# 27128_27256_Multi-ROM_Rev_4.net
KiCad netlist of a schematic drawn in EAGLE
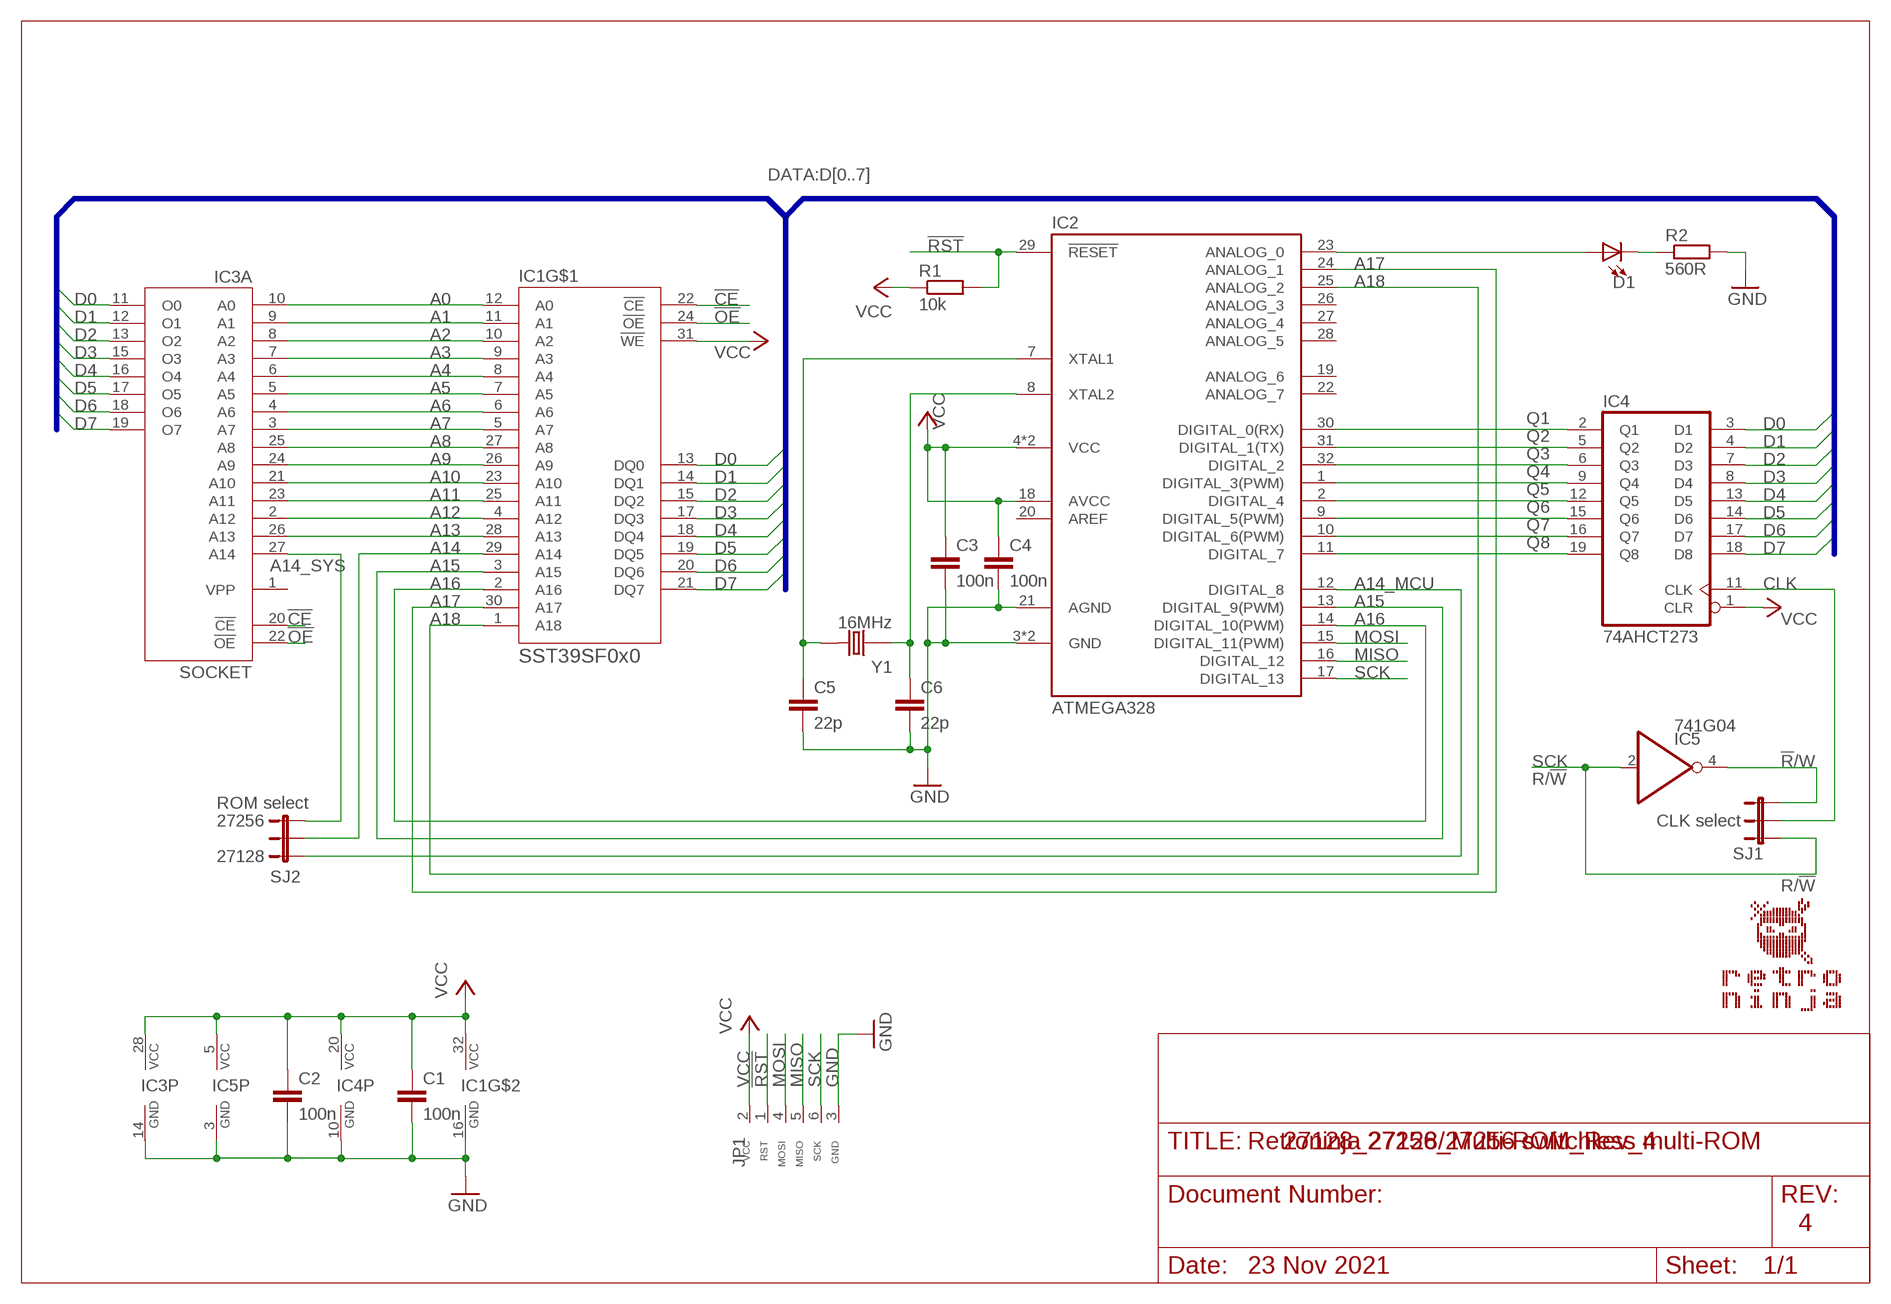
[diagram p0: schematic, sheet 1]

(export (version "E")
  (design (tool "Eeschema 10.0.6"))
  (components
    (comp (ref "C1")
      (value "100n")
      (footprint "eagle-import:C0805")
      (libsource (lib "eagle-import") (part "C-EUC0805"))
    )
    (comp (ref "C2")
      (value "100n")
      (footprint "eagle-import:C0805")
      (libsource (lib "eagle-import") (part "C-EUC0805"))
    )
    (comp (ref "C3")
      (value "100n")
      (footprint "eagle-import:C0805")
      (libsource (lib "eagle-import") (part "C-EUC0805"))
    )
    (comp (ref "C4")
      (value "100n")
      (footprint "eagle-import:C0805")
      (libsource (lib "eagle-import") (part "C-EUC0805"))
    )
    (comp (ref "C5")
      (value "22p")
      (footprint "eagle-import:C0805")
      (libsource (lib "eagle-import") (part "C-EUC0805"))
    )
    (comp (ref "C6")
      (value "22p")
      (footprint "eagle-import:C0805")
      (libsource (lib "eagle-import") (part "C-EUC0805"))
    )
    (comp (ref "D1")
      (value "LED_0805")
      (footprint "eagle-import:LED0805")
      (libsource (lib "eagle-import") (part "LED_0805"))
    )
    (comp (ref "IC1")
      (value "SST39SF0x0")
      (footprint "eagle-import:PLCC32_SHORT")
      (libsource (lib "eagle-import") (part "SST39XX040_PLCC_SHORT"))
    )
    (comp (ref "IC2")
      (value "ATMEGA328")
      (footprint "eagle-import:TQFP32")
      (libsource (lib "eagle-import") (part "ARDUINO_168_328_TQFP"))
    )
    (comp (ref "IC3")
      (value "SOCKET")
      (footprint "eagle-import:DIL28-6_DOWNPINS")
      (libsource (lib "eagle-import") (part "27C256_DOWNPINS"))
    )
    (comp (ref "IC4")
      (value "74AHCT273")
      (footprint "eagle-import:SO20")
      (libsource (lib "eagle-import") (part "74273NS"))
    )
    (comp (ref "IC5")
      (value "741G04")
      (footprint "eagle-import:SOT23-5")
      (libsource (lib "eagle-import") (part "741G04_SOT23"))
    )
    (comp (ref "JP1")
      (value "ICSP_CONNECTOR_TL866_RIGHT2")
      (footprint "eagle-import:HEADER_1X6_RIGHT")
      (libsource (lib "eagle-import") (part "ICSP_CONNECTOR_TL866_RIGHT2"))
    )
    (comp (ref "R1")
      (value "10k")
      (footprint "eagle-import:R0805")
      (libsource (lib "eagle-import") (part "R-EU_R0805"))
    )
    (comp (ref "R2")
      (value "560R")
      (footprint "eagle-import:R0805")
      (libsource (lib "eagle-import") (part "R-EU_R0805"))
    )
    (comp (ref "SJ1")
      (value "JUMPER-3SJ")
      (footprint "eagle-import:SJ-3")
      (libsource (lib "eagle-import") (part "JUMPER-3SJ"))
    )
    (comp (ref "SJ2")
      (value "JUMPER-3SJ")
      (footprint "eagle-import:SJ-3")
      (libsource (lib "eagle-import") (part "JUMPER-3SJ"))
    )
    (comp (ref "Y1")
      (value "16MHz")
      (footprint "eagle-import:CRYSTAL_SMD-2_7X4X2.3")
      (libsource (lib "eagle-import") (part "CRYSTAL"))
    )
  )
  (nets
    (net (code "9") (name "/A0") (class "Default")
      (node (ref "IC1") (pin "12") (pinfunction "A0_12") (pintype "input"))
      (node (ref "IC3") (pin "10") (pinfunction "A0_10") (pintype "input"))
    )
    (net (code "10") (name "/A1") (class "Default")
      (node (ref "IC1") (pin "11") (pinfunction "A1_11") (pintype "input"))
      (node (ref "IC3") (pin "9") (pinfunction "A1_9") (pintype "input"))
    )
    (net (code "11") (name "/A2") (class "Default")
      (node (ref "IC1") (pin "10") (pinfunction "A2_10") (pintype "input"))
      (node (ref "IC3") (pin "8") (pinfunction "A2_8") (pintype "input"))
    )
    (net (code "12") (name "/A3") (class "Default")
      (node (ref "IC1") (pin "9") (pinfunction "A3_9") (pintype "input"))
      (node (ref "IC3") (pin "7") (pinfunction "A3_7") (pintype "input"))
    )
    (net (code "13") (name "/A4") (class "Default")
      (node (ref "IC1") (pin "8") (pinfunction "A4_8") (pintype "input"))
      (node (ref "IC3") (pin "6") (pinfunction "A4_6") (pintype "input"))
    )
    (net (code "14") (name "/A5") (class "Default")
      (node (ref "IC1") (pin "7") (pinfunction "A5_7") (pintype "input"))
      (node (ref "IC3") (pin "5") (pinfunction "A5_5") (pintype "input"))
    )
    (net (code "15") (name "/A6") (class "Default")
      (node (ref "IC1") (pin "6") (pinfunction "A6_6") (pintype "input"))
      (node (ref "IC3") (pin "4") (pinfunction "A6_4") (pintype "input"))
    )
    (net (code "16") (name "/A7") (class "Default")
      (node (ref "IC1") (pin "5") (pinfunction "A7_5") (pintype "input"))
      (node (ref "IC3") (pin "3") (pinfunction "A7_3") (pintype "input"))
    )
    (net (code "17") (name "/A8") (class "Default")
      (node (ref "IC1") (pin "27") (pinfunction "A8_27") (pintype "input"))
      (node (ref "IC3") (pin "25") (pinfunction "A8_25") (pintype "input"))
    )
    (net (code "18") (name "/A9") (class "Default")
      (node (ref "IC1") (pin "26") (pinfunction "A9_26") (pintype "input"))
      (node (ref "IC3") (pin "24") (pinfunction "A9_24") (pintype "input"))
    )
    (net (code "19") (name "/A10") (class "Default")
      (node (ref "IC1") (pin "23") (pinfunction "A10_23") (pintype "input"))
      (node (ref "IC3") (pin "21") (pinfunction "A10_21") (pintype "input"))
    )
    (net (code "20") (name "/A11") (class "Default")
      (node (ref "IC1") (pin "25") (pinfunction "A11_25") (pintype "input"))
      (node (ref "IC3") (pin "23") (pinfunction "A11_23") (pintype "input"))
    )
    (net (code "21") (name "/A12") (class "Default")
      (node (ref "IC1") (pin "4") (pinfunction "A12_4") (pintype "input"))
      (node (ref "IC3") (pin "2") (pinfunction "A12_2") (pintype "input"))
    )
    (net (code "22") (name "/A13") (class "Default")
      (node (ref "IC1") (pin "28") (pinfunction "A13_28") (pintype "input"))
      (node (ref "IC3") (pin "26") (pinfunction "A13_26") (pintype "input"))
    )
    (net (code "23") (name "/A14") (class "Default")
      (node (ref "IC1") (pin "29") (pinfunction "A14_29") (pintype "input"))
      (node (ref "SJ2") (pin "2") (pinfunction "2_2") (pintype "passive"))
    )
    (net (code "24") (name "/A14_MCU") (class "Default")
      (node (ref "IC2") (pin "12") (pinfunction "DIGITAL_8_12") (pintype "bidirectional"))
      (node (ref "SJ2") (pin "1") (pinfunction "1_1") (pintype "passive"))
    )
    (net (code "25") (name "/A14_SYS") (class "Default")
      (node (ref "IC3") (pin "27") (pinfunction "A14_27") (pintype "input"))
      (node (ref "SJ2") (pin "3") (pinfunction "3_3") (pintype "passive"))
    )
    (net (code "26") (name "/A15") (class "Default")
      (node (ref "IC1") (pin "3") (pinfunction "A15_3") (pintype "input"))
      (node (ref "IC2") (pin "13") (pinfunction "DIGITAL_9(PWM)_13") (pintype "bidirectional"))
    )
    (net (code "27") (name "/A16") (class "Default")
      (node (ref "IC1") (pin "2") (pinfunction "A16_2") (pintype "input"))
      (node (ref "IC2") (pin "14") (pinfunction "DIGITAL_10(PWM)_14") (pintype "bidirectional"))
    )
    (net (code "28") (name "/A17") (class "Default")
      (node (ref "IC1") (pin "30") (pinfunction "A17_30") (pintype "input"))
      (node (ref "IC2") (pin "24") (pinfunction "ANALOG_1_24") (pintype "bidirectional"))
    )
    (net (code "29") (name "/A18") (class "Default")
      (node (ref "IC1") (pin "1") (pinfunction "A18_1") (pintype "input"))
      (node (ref "IC2") (pin "25") (pinfunction "ANALOG_2_25") (pintype "bidirectional"))
    )
    (net (code "30") (name "/CLK") (class "Default")
      (node (ref "IC4") (pin "11") (pinfunction "CLK_11") (pintype "input"))
      (node (ref "SJ1") (pin "2") (pinfunction "2_2") (pintype "passive"))
    )
    (net (code "31") (name "/D0") (class "Default")
      (node (ref "IC1") (pin "13") (pinfunction "DQ0_13") (pintype "bidirectional"))
      (node (ref "IC3") (pin "11") (pinfunction "O0_11") (pintype "tri_state"))
      (node (ref "IC4") (pin "3") (pinfunction "D1_3") (pintype "input"))
    )
    (net (code "32") (name "/D1") (class "Default")
      (node (ref "IC1") (pin "14") (pinfunction "DQ1_14") (pintype "bidirectional"))
      (node (ref "IC3") (pin "12") (pinfunction "O1_12") (pintype "tri_state"))
      (node (ref "IC4") (pin "4") (pinfunction "D2_4") (pintype "input"))
    )
    (net (code "33") (name "/D2") (class "Default")
      (node (ref "IC1") (pin "15") (pinfunction "DQ2_15") (pintype "bidirectional"))
      (node (ref "IC3") (pin "13") (pinfunction "O2_13") (pintype "tri_state"))
      (node (ref "IC4") (pin "7") (pinfunction "D3_7") (pintype "input"))
    )
    (net (code "34") (name "/D3") (class "Default")
      (node (ref "IC1") (pin "17") (pinfunction "DQ3_17") (pintype "bidirectional"))
      (node (ref "IC3") (pin "15") (pinfunction "O3_15") (pintype "tri_state"))
      (node (ref "IC4") (pin "8") (pinfunction "D4_8") (pintype "input"))
    )
    (net (code "35") (name "/D4") (class "Default")
      (node (ref "IC1") (pin "18") (pinfunction "DQ4_18") (pintype "bidirectional"))
      (node (ref "IC3") (pin "16") (pinfunction "O4_16") (pintype "tri_state"))
      (node (ref "IC4") (pin "13") (pinfunction "D5_13") (pintype "input"))
    )
    (net (code "36") (name "/D5") (class "Default")
      (node (ref "IC1") (pin "19") (pinfunction "DQ5_19") (pintype "bidirectional"))
      (node (ref "IC3") (pin "17") (pinfunction "O5_17") (pintype "tri_state"))
      (node (ref "IC4") (pin "14") (pinfunction "D6_14") (pintype "input"))
    )
    (net (code "37") (name "/D6") (class "Default")
      (node (ref "IC1") (pin "20") (pinfunction "DQ6_20") (pintype "bidirectional"))
      (node (ref "IC3") (pin "18") (pinfunction "O6_18") (pintype "tri_state"))
      (node (ref "IC4") (pin "17") (pinfunction "D7_17") (pintype "input"))
    )
    (net (code "38") (name "/D7") (class "Default")
      (node (ref "IC1") (pin "21") (pinfunction "DQ7_21") (pintype "bidirectional"))
      (node (ref "IC3") (pin "19") (pinfunction "O7_19") (pintype "tri_state"))
      (node (ref "IC4") (pin "18") (pinfunction "D8_18") (pintype "input"))
    )
    (net (code "40") (name "/MISO") (class "Default")
      (node (ref "IC2") (pin "16") (pinfunction "DIGITAL_12_16") (pintype "bidirectional"))
      (node (ref "JP1") (pin "5") (pinfunction "MISO_5") (pintype "output"))
    )
    (net (code "41") (name "/MOSI") (class "Default")
      (node (ref "IC2") (pin "15") (pinfunction "DIGITAL_11(PWM)_15") (pintype "bidirectional"))
      (node (ref "JP1") (pin "4") (pinfunction "MOSI_4") (pintype "input"))
    )
    (net (code "42") (name "/Q1") (class "Default")
      (node (ref "IC2") (pin "30") (pinfunction "DIGITAL_0(RX)_30") (pintype "bidirectional"))
      (node (ref "IC4") (pin "2") (pinfunction "Q1_2") (pintype "output"))
    )
    (net (code "43") (name "/Q2") (class "Default")
      (node (ref "IC2") (pin "31") (pinfunction "DIGITAL_1(TX)_31") (pintype "bidirectional"))
      (node (ref "IC4") (pin "5") (pinfunction "Q2_5") (pintype "output"))
    )
    (net (code "44") (name "/Q3") (class "Default")
      (node (ref "IC2") (pin "32") (pinfunction "DIGITAL_2_32") (pintype "bidirectional"))
      (node (ref "IC4") (pin "6") (pinfunction "Q3_6") (pintype "output"))
    )
    (net (code "45") (name "/Q4") (class "Default")
      (node (ref "IC2") (pin "1") (pinfunction "DIGITAL_3(PWM)_1") (pintype "bidirectional"))
      (node (ref "IC4") (pin "9") (pinfunction "Q4_9") (pintype "output"))
    )
    (net (code "46") (name "/Q5") (class "Default")
      (node (ref "IC2") (pin "2") (pinfunction "DIGITAL_4_2") (pintype "bidirectional"))
      (node (ref "IC4") (pin "12") (pinfunction "Q5_12") (pintype "output"))
    )
    (net (code "47") (name "/Q6") (class "Default")
      (node (ref "IC2") (pin "9") (pinfunction "DIGITAL_5(PWM)_9") (pintype "bidirectional"))
      (node (ref "IC4") (pin "15") (pinfunction "Q6_15") (pintype "output"))
    )
    (net (code "48") (name "/Q7") (class "Default")
      (node (ref "IC2") (pin "10") (pinfunction "DIGITAL_6(PWM)_10") (pintype "bidirectional"))
      (node (ref "IC4") (pin "16") (pinfunction "Q7_16") (pintype "output"))
    )
    (net (code "49") (name "/Q8") (class "Default")
      (node (ref "IC2") (pin "11") (pinfunction "DIGITAL_7_11") (pintype "bidirectional"))
      (node (ref "IC4") (pin "19") (pinfunction "Q8_19") (pintype "output"))
    )
    (net (code "50") (name "/SCK") (class "Default")
      (node (ref "IC2") (pin "17") (pinfunction "DIGITAL_13_17") (pintype "bidirectional"))
      (node (ref "IC5") (pin "2") (pinfunction "I_2") (pintype "input"))
      (node (ref "JP1") (pin "6") (pinfunction "SCK_6") (pintype "input"))
      (node (ref "SJ1") (pin "1") (pinfunction "1_1") (pintype "passive"))
    )
    (net (code "51") (name "/VPP") (class "Default")
      (node (ref "IC3") (pin "1") (pinfunction "VPP_1") (pintype "power_in"))
    )
    (net (code "52") (name "/~{CE}") (class "Default")
      (node (ref "IC1") (pin "22") (pinfunction "~{CE}_22") (pintype "input"))
      (node (ref "IC3") (pin "20") (pinfunction "~{CE}_20") (pintype "input"))
    )
    (net (code "53") (name "/~{OE}") (class "Default")
      (node (ref "IC1") (pin "24") (pinfunction "~{OE}_24") (pintype "input"))
      (node (ref "IC3") (pin "22") (pinfunction "~{OE}_22") (pintype "input"))
    )
    (net (code "54") (name "/~{RST}") (class "Default")
      (node (ref "IC2") (pin "29") (pinfunction "~{RESET}_29") (pintype "bidirectional"))
      (node (ref "JP1") (pin "1") (pinfunction "RST_1") (pintype "input"))
      (node (ref "R1") (pin "2") (pinfunction "2_2") (pintype "passive"))
    )
    (net (code "55") (name "/~{R}{slash}W") (class "Default")
      (node (ref "IC5") (pin "4") (pinfunction "O_4") (pintype "output"))
      (node (ref "SJ1") (pin "3") (pinfunction "3_3") (pintype "passive"))
    )
    (net (code "56") (name "GND") (class "Default")
      (node (ref "C1") (pin "2") (pinfunction "2_2") (pintype "passive"))
      (node (ref "C2") (pin "2") (pinfunction "2_2") (pintype "passive"))
      (node (ref "C3") (pin "2") (pinfunction "2_2") (pintype "passive"))
      (node (ref "C4") (pin "2") (pinfunction "2_2") (pintype "passive"))
      (node (ref "C5") (pin "2") (pinfunction "2_2") (pintype "passive"))
      (node (ref "C6") (pin "2") (pinfunction "2_2") (pintype "passive"))
      (node (ref "IC1") (pin "16") (pinfunction "GND_16") (pintype "power_in"))
      (node (ref "IC2") (pin "21") (pinfunction "AGND_21") (pintype "passive"))
      (node (ref "IC2") (pin "3") (pinfunction "GND_3") (pintype "passive"))
      (node (ref "IC2") (pin "5") (pinfunction "GND_5") (pintype "passive"))
      (node (ref "IC3") (pin "14") (pinfunction "GND_14") (pintype "power_in"))
      (node (ref "IC4") (pin "10") (pinfunction "GND_10") (pintype "power_in"))
      (node (ref "IC5") (pin "3") (pinfunction "GND_3") (pintype "power_in"))
      (node (ref "JP1") (pin "3") (pinfunction "GND_3") (pintype "power_in"))
      (node (ref "R2") (pin "2") (pinfunction "2_2") (pintype "passive"))
    )
    (net (code "57") (name "Net-(D1-PadC)") (class "Default")
      (node (ref "D1") (pin "C") (pinfunction "C_C") (pintype "passive"))
      (node (ref "R2") (pin "1") (pinfunction "1_1") (pintype "passive"))
    )
    (net (code "58") (name "Net-(IC2-ANALOG_0)") (class "Default")
      (node (ref "D1") (pin "A") (pinfunction "A_A") (pintype "passive"))
      (node (ref "IC2") (pin "23") (pinfunction "ANALOG_0_23") (pintype "bidirectional"))
    )
    (net (code "59") (name "Net-(IC2-XTAL1)") (class "Default")
      (node (ref "C5") (pin "1") (pinfunction "1_1") (pintype "passive"))
      (node (ref "IC2") (pin "7") (pinfunction "XTAL1_7") (pintype "bidirectional"))
      (node (ref "Y1") (pin "2") (pinfunction "2_2") (pintype "passive"))
    )
    (net (code "60") (name "Net-(IC2-XTAL2)") (class "Default")
      (node (ref "C6") (pin "1") (pinfunction "1_1") (pintype "passive"))
      (node (ref "IC2") (pin "8") (pinfunction "XTAL2_8") (pintype "bidirectional"))
      (node (ref "Y1") (pin "1") (pinfunction "1_1") (pintype "passive"))
    )
    (net (code "61") (name "VCC") (class "Default")
      (node (ref "C1") (pin "1") (pinfunction "1_1") (pintype "passive"))
      (node (ref "C2") (pin "1") (pinfunction "1_1") (pintype "passive"))
      (node (ref "C3") (pin "1") (pinfunction "1_1") (pintype "passive"))
      (node (ref "C4") (pin "1") (pinfunction "1_1") (pintype "passive"))
      (node (ref "IC1") (pin "31") (pinfunction "~{WE}_31") (pintype "input"))
      (node (ref "IC1") (pin "32") (pinfunction "VCC_32") (pintype "power_in"))
      (node (ref "IC2") (pin "18") (pinfunction "AVCC_18") (pintype "passive"))
      (node (ref "IC2") (pin "4") (pinfunction "VCC_4") (pintype "passive"))
      (node (ref "IC2") (pin "6") (pinfunction "VCC_6") (pintype "passive"))
      (node (ref "IC3") (pin "28") (pinfunction "VCC_28") (pintype "power_in"))
      (node (ref "IC4") (pin "1") (pinfunction "CLR_1") (pintype "input"))
      (node (ref "IC4") (pin "20") (pinfunction "VCC_20") (pintype "power_in"))
      (node (ref "IC5") (pin "5") (pinfunction "VCC_5") (pintype "power_in"))
      (node (ref "JP1") (pin "2") (pinfunction "VCC_2") (pintype "power_in"))
      (node (ref "R1") (pin "1") (pinfunction "1_1") (pintype "passive"))
    )
    (net (code "62") (name "unconnected-(IC2-ANALOG_3-Pad26)") (class "Default")
      (node (ref "IC2") (pin "26") (pinfunction "ANALOG_3_26") (pintype "bidirectional"))
    )
    (net (code "63") (name "unconnected-(IC2-ANALOG_4-Pad27)") (class "Default")
      (node (ref "IC2") (pin "27") (pinfunction "ANALOG_4_27") (pintype "bidirectional"))
    )
    (net (code "64") (name "unconnected-(IC2-ANALOG_5-Pad28)") (class "Default")
      (node (ref "IC2") (pin "28") (pinfunction "ANALOG_5_28") (pintype "bidirectional"))
    )
    (net (code "65") (name "unconnected-(IC2-ANALOG_6-Pad19)") (class "Default")
      (node (ref "IC2") (pin "19") (pinfunction "ANALOG_6_19") (pintype "bidirectional"))
    )
    (net (code "66") (name "unconnected-(IC2-ANALOG_7-Pad22)") (class "Default")
      (node (ref "IC2") (pin "22") (pinfunction "ANALOG_7_22") (pintype "bidirectional"))
    )
    (net (code "67") (name "unconnected-(IC2-AREF-Pad20)") (class "Default")
      (node (ref "IC2") (pin "20") (pinfunction "AREF_20") (pintype "passive"))
    )
  )
)
